# Fdbk_2.net
KiCad netlist of a schematic drawn in Altium Designer
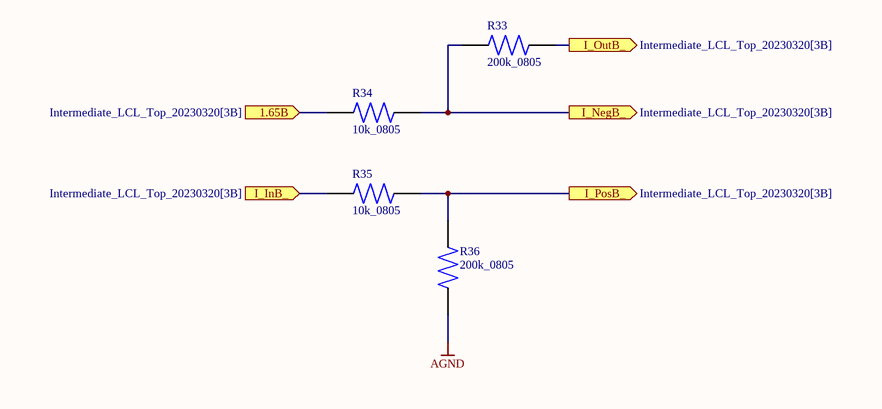
[diagram p0: Fdbk_2.SchDoc]

(export (version "E")
  (design (tool "Eeschema 10.0.6"))
  (components
    (comp (ref "R33")
      (value "200k_0805")
      (footprint "FYP_Components:0805 Resistor")
      (description "SMD Chip Resistor, 200 kohm, ± 1%, 125 mW, 0805 [2012 Metric], Thick Film, General Purpose")
      (fields (field (name "MF") "Bourns") (field (name "MP") "CRE2512-FZ-R007E-3"))
      (libsource (lib "FYP_Components") (part "CRCW0805200KFKEA"))
    )
    (comp (ref "R34")
      (value "10k_0805")
      (footprint "FYP_Components:0805 Resistor")
      (description "SMD Chip Resistor, 10 kohm, ± 1%, 125 mW, 0805 [2012 Metric], Thick Film, General Purpose")
      (fields (field (name "MF") "Bourns") (field (name "MP") "CRE2512-FZ-R007E-3"))
      (libsource (lib "FYP_Components") (part "CRCW080510K0FKEA"))
    )
    (comp (ref "R35")
      (value "10k_0805")
      (footprint "FYP_Components:0805 Resistor")
      (description "SMD Chip Resistor, 10 kohm, ± 1%, 125 mW, 0805 [2012 Metric], Thick Film, General Purpose")
      (fields (field (name "MF") "Bourns") (field (name "MP") "CRE2512-FZ-R007E-3"))
      (libsource (lib "FYP_Components") (part "CRCW080510K0FKEA"))
    )
    (comp (ref "R36")
      (value "200k_0805")
      (footprint "FYP_Components:0805 Resistor")
      (description "SMD Chip Resistor, 200 kohm, ± 1%, 125 mW, 0805 [2012 Metric], Thick Film, General Purpose")
      (fields (field (name "MF") "Bourns") (field (name "MP") "CRE2512-FZ-R007E-3"))
      (libsource (lib "FYP_Components") (part "CRCW0805200KFKEA"))
    )
  )
  (nets
    (net (code "1") (name "/1.65B") (class "Default")
      (node (ref "R34") (pin "1") (pinfunction "1_1") (pintype "passive"))
    )
    (net (code "2") (name "/I_InB_") (class "Default")
      (node (ref "R35") (pin "1") (pinfunction "1_1") (pintype "passive"))
    )
    (net (code "3") (name "/I_NegB_") (class "Default")
      (node (ref "R33") (pin "1") (pinfunction "1_1") (pintype "passive"))
      (node (ref "R34") (pin "2") (pinfunction "2_2") (pintype "passive"))
    )
    (net (code "4") (name "/I_OutB_") (class "Default")
      (node (ref "R33") (pin "2") (pinfunction "2_2") (pintype "passive"))
    )
    (net (code "5") (name "/I_PosB_") (class "Default")
      (node (ref "R35") (pin "2") (pinfunction "2_2") (pintype "passive"))
      (node (ref "R36") (pin "2") (pinfunction "2_2") (pintype "passive"))
    )
    (net (code "6") (name "AGND") (class "Default")
      (node (ref "R36") (pin "1") (pinfunction "1_1") (pintype "passive"))
    )
  )
)
